# ESD-MATT.net
KiCad netlist of a schematic drawn in Altium Designer
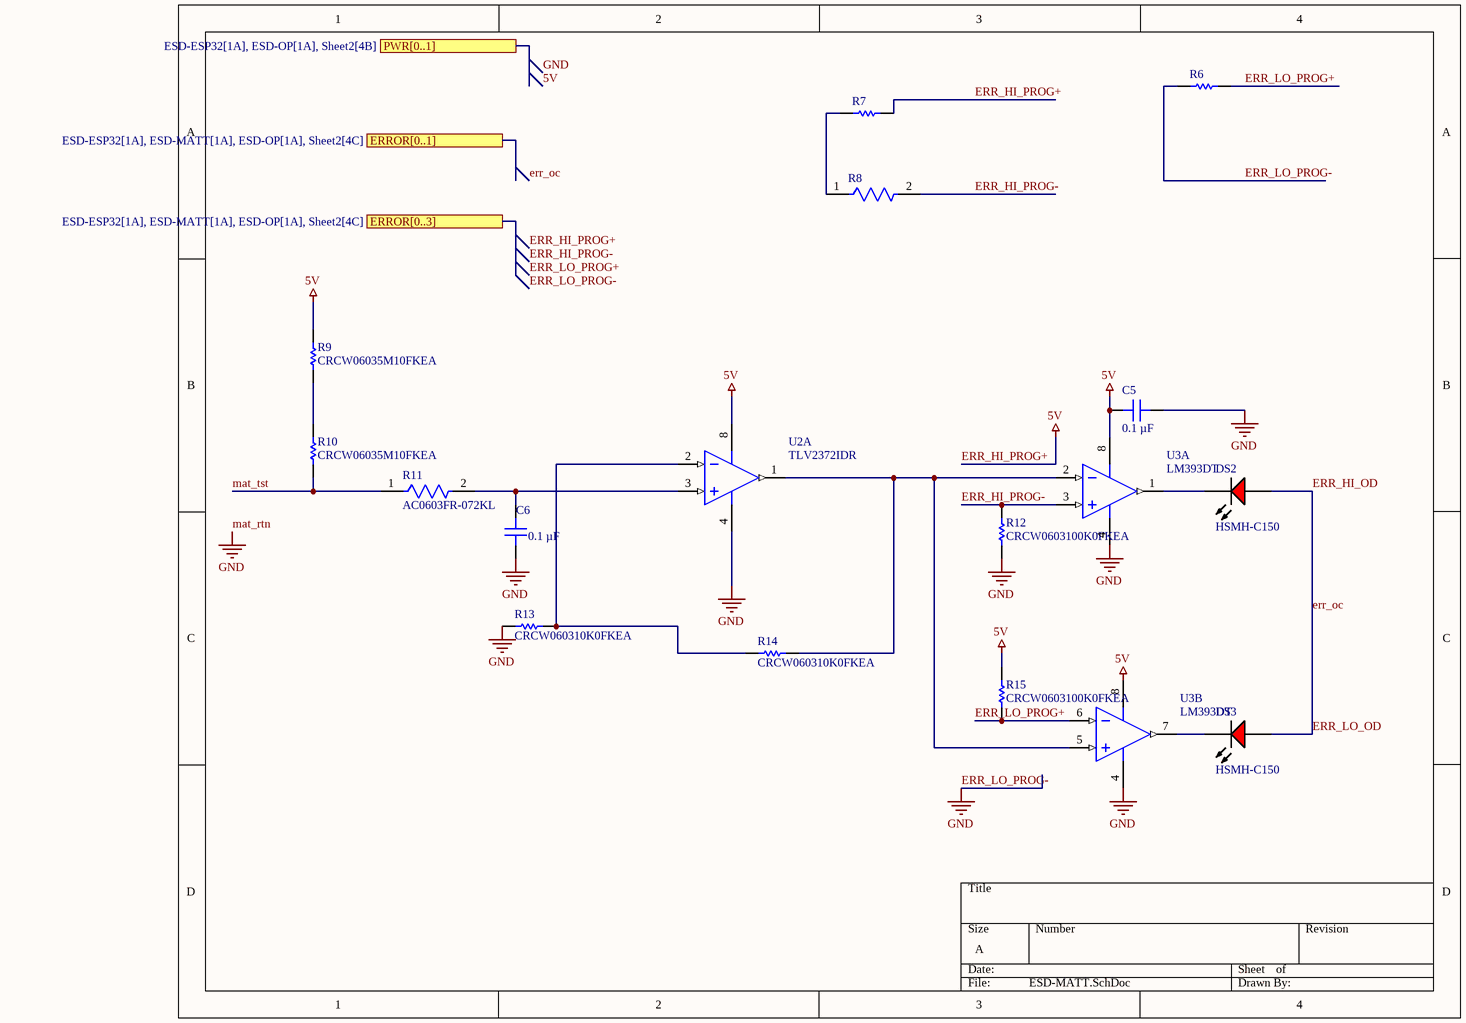
[diagram p0: ESD-MATT.SchDoc]

(export (version "E")
  (design (tool "Eeschema 10.0.6"))
  (components
    (comp (ref "C5")
      (value "0.1 µF")
      (footprint "CAP 0603_1608")
      (description "CAP CER 0.1UF 50V X7R 0603")
      (fields (field (name "PART NUMBER") "C0603X104J5RACAUTO") (field (name "MANUFACTURER") "KEMET"))
      (libsource (lib "Celestial Altium Library - altium_library") (part "Capacitor"))
    )
    (comp (ref "C6")
      (value "0.1 µF")
      (footprint "CAP 0603_1608")
      (description "CAP CER 0.1UF 50V X7R 0603")
      (fields (field (name "PART NUMBER") "C0603X104J5RACAUTO") (field (name "MANUFACTURER") "KEMET"))
      (libsource (lib "Celestial Altium Library - altium_library") (part "Capacitor"))
    )
    (comp (ref "DS2")
      (value "HSMH-C150")
      (footprint "AVAG-HSMX-C150_V")
      (description "LED Uni-Color Red, 65 mW, 25 mA, -40 to 85 degC, 2-Pin SMD, RoHS, Tape and Reel")
      (fields (field (name "MANUFACTURER") "Avago"))
      (libsource (lib "Altium Content Vault") (part "LED-RED-AK-2"))
    )
    (comp (ref "DS3")
      (value "HSMH-C150")
      (footprint "AVAG-HSMX-C150_V")
      (description "LED Uni-Color Red, 65 mW, 25 mA, -40 to 85 degC, 2-Pin SMD, RoHS, Tape and Reel")
      (fields (field (name "MANUFACTURER") "Avago"))
      (libsource (lib "Altium Content Vault") (part "LED-RED-AK-2"))
    )
    (comp (ref "R6")
      (value "CRCW060310K0FKEA")
      (footprint "RESC1609X50X30NL8T20")
      (description "Chip Resistor, 10 KOhm, +/- 1%, 100 mW, -55 to 155 degC, 0603 (1608 Metric), RoHS, Tape and Reel")
      (fields (field (name "MANUFACTURER") "Vishay Semiconductor"))
      (libsource (lib "Altium Content Vault") (part "RES-2"))
    )
    (comp (ref "R7")
      (value "CRCW060310K0FKEA")
      (footprint "RESC1609X50X30NL8T20")
      (description "Chip Resistor, 10 KOhm, +/- 1%, 100 mW, -55 to 155 degC, 0603 (1608 Metric), RoHS, Tape and Reel")
      (fields (field (name "MANUFACTURER") "Vishay Semiconductor"))
      (libsource (lib "Altium Content Vault") (part "RES-2"))
    )
    (comp (ref "R8")
      (value "AC0603FR-072KL")
      (footprint "FP-AC0603-IPC_B")
      (description "RES 2kΩ 1.00% 0.1W 0603")
      (fields (field (name "TOLERANCE") "1%"))
      (libsource (lib "Altium Content Vault") (part "1029c3af85768c4190bb7ad29bc67b5"))
    )
    (comp (ref "R9")
      (value "CRCW06035M10FKEA")
      (footprint "RESC1609X50X30NL10T20")
      (fields (field (name "MANUFACTURER") "Vishay Dale"))
      (libsource (lib "Altium Content Vault") (part "RES"))
    )
    (comp (ref "R10")
      (value "CRCW06035M10FKEA")
      (footprint "RESC1609X50X30NL10T20")
      (fields (field (name "MANUFACTURER") "Vishay Dale"))
      (libsource (lib "Altium Content Vault") (part "RES"))
    )
    (comp (ref "R11")
      (value "AC0603FR-072KL")
      (footprint "FP-AC0603-IPC_B")
      (description "RES 2kΩ 1.00% 0.1W 0603")
      (fields (field (name "TOLERANCE") "1%"))
      (libsource (lib "Altium Content Vault") (part "1029c3af85768c4190bb7ad29bc67b5"))
    )
    (comp (ref "R12")
      (value "CRCW0603100K0FKEA")
      (footprint "RESC1609X50X30NL8T20")
      (description "Chip Resistor, 100 KOhm, +/- 1%, 100 mW, -55 to 155 degC, 0603 (1608 Metric), RoHS, Tape and Reel")
      (fields (field (name "MANUFACTURER") "Vishay Semiconductor"))
      (libsource (lib "Altium Content Vault") (part "RES-2"))
    )
    (comp (ref "R13")
      (value "CRCW060310K0FKEA")
      (footprint "RESC1609X50X30NL8T20")
      (description "Chip Resistor, 10 KOhm, +/- 1%, 100 mW, -55 to 155 degC, 0603 (1608 Metric), RoHS, Tape and Reel")
      (fields (field (name "MANUFACTURER") "Vishay Semiconductor"))
      (libsource (lib "Altium Content Vault") (part "RES-2"))
    )
    (comp (ref "R14")
      (value "CRCW060310K0FKEA")
      (footprint "RESC1609X50X30NL8T20")
      (description "Chip Resistor, 10 KOhm, +/- 1%, 100 mW, -55 to 155 degC, 0603 (1608 Metric), RoHS, Tape and Reel")
      (fields (field (name "MANUFACTURER") "Vishay Semiconductor"))
      (libsource (lib "Altium Content Vault") (part "RES-2"))
    )
    (comp (ref "R15")
      (value "CRCW0603100K0FKEA")
      (footprint "RESC1609X50X30NL8T20")
      (description "Chip Resistor, 100 KOhm, +/- 1%, 100 mW, -55 to 155 degC, 0603 (1608 Metric), RoHS, Tape and Reel")
      (fields (field (name "MANUFACTURER") "Vishay Semiconductor"))
      (libsource (lib "Altium Content Vault") (part "RES-2"))
    )
    (comp (ref "U2")
      (value "TLV2372IDR")
      (footprint "D0008A_M")
      (fields (field (name "MANUFACTURER") "Texas Instruments"))
      (libsource (lib "Altium Content Vault") (part "TI-TLV_TLC-8"))
    )
    (comp (ref "U3")
      (value "LM393DT")
      (footprint "STM-SO-8_D_L")
      (description "Low-Power, Dual-Voltage Comparator, 2 to 36 V, 0 to 70 degC, 8-Pin SOIC (SO), RoHS, Tape and Reel")
      (fields (field (name "MANUFACTURER") "STMicroelectronics"))
      (libsource (lib "Altium Content Vault") (part "STM-LM393-SO8"))
    )
  )
  (nets
    (net (code "9") (name "/ERR_HI_OD") (class "Default")
      (node (ref "DS2") (pin "1") (pinfunction "A_1") (pintype "passive"))
      (node (ref "DS3") (pin "1") (pinfunction "A_1") (pintype "passive"))
    )
    (net (code "10") (name "/ERR_HI_PROG-") (class "Default")
      (node (ref "R12") (pin "1") (pinfunction "1_1") (pintype "passive"))
      (node (ref "R8") (pin "2") (pinfunction "2_2") (pintype "passive"))
      (node (ref "U3") (pin "3") (pinfunction "IN1+_3") (pintype "input"))
    )
    (net (code "11") (name "/ERR_LO_PROG+") (class "Default")
      (node (ref "R15") (pin "2") (pinfunction "2_2") (pintype "passive"))
      (node (ref "R6") (pin "2") (pinfunction "2_2") (pintype "passive"))
      (node (ref "U3") (pin "6") (pinfunction "IN2-_6") (pintype "input"))
    )
    (net (code "13") (name "/mat_tst") (class "Default")
      (node (ref "R10") (pin "1") (pinfunction "1_1") (pintype "passive"))
      (node (ref "R11") (pin "1") (pinfunction "1_1") (pintype "passive"))
    )
    (net (code "14") (name "5V") (class "Default")
      (node (ref "C5") (pin "2") (pinfunction "2_2") (pintype "passive"))
      (node (ref "R15") (pin "1") (pinfunction "1_1") (pintype "passive"))
      (node (ref "R7") (pin "2") (pinfunction "2_2") (pintype "passive"))
      (node (ref "R9") (pin "2") (pinfunction "2_2") (pintype "passive"))
      (node (ref "U2") (pin "8") (pinfunction "VDD_8") (pintype "power_in"))
      (node (ref "U3") (pin "8") (pinfunction "VCC+_8") (pintype "power_in"))
    )
    (net (code "15") (name "GND") (class "Default")
      (node (ref "C5") (pin "1") (pinfunction "1_1") (pintype "passive"))
      (node (ref "C6") (pin "1") (pinfunction "1_1") (pintype "passive"))
      (node (ref "R12") (pin "2") (pinfunction "2_2") (pintype "passive"))
      (node (ref "R13") (pin "1") (pinfunction "1_1") (pintype "passive"))
      (node (ref "R6") (pin "1") (pinfunction "1_1") (pintype "passive"))
      (node (ref "U2") (pin "4") (pinfunction "GND_4") (pintype "power_in"))
      (node (ref "U3") (pin "4") (pinfunction "VCC-_4") (pintype "power_in"))
    )
    (net (code "16") (name "Net-(DS2-K)") (class "Default")
      (node (ref "DS2") (pin "2") (pinfunction "K_2") (pintype "passive"))
      (node (ref "U3") (pin "1") (pinfunction "OUT1_1") (pintype "output"))
    )
    (net (code "17") (name "Net-(DS3-K)") (class "Default")
      (node (ref "DS3") (pin "2") (pinfunction "K_2") (pintype "passive"))
      (node (ref "U3") (pin "7") (pinfunction "OUT2_7") (pintype "output"))
    )
    (net (code "18") (name "Net-(R7-Pad1)") (class "Default")
      (node (ref "R7") (pin "1") (pinfunction "1_1") (pintype "passive"))
      (node (ref "R8") (pin "1") (pinfunction "1_1") (pintype "passive"))
    )
    (net (code "19") (name "Net-(R10-Pad2)") (class "Default")
      (node (ref "R10") (pin "2") (pinfunction "2_2") (pintype "passive"))
      (node (ref "R9") (pin "1") (pinfunction "1_1") (pintype "passive"))
    )
    (net (code "20") (name "Net-(U2A-IN1+)") (class "Default")
      (node (ref "C6") (pin "2") (pinfunction "2_2") (pintype "passive"))
      (node (ref "R11") (pin "2") (pinfunction "2_2") (pintype "passive"))
      (node (ref "U2") (pin "3") (pinfunction "IN1+_3") (pintype "input"))
    )
    (net (code "21") (name "Net-(U2A-IN1-)") (class "Default")
      (node (ref "R13") (pin "2") (pinfunction "2_2") (pintype "passive"))
      (node (ref "R14") (pin "1") (pinfunction "1_1") (pintype "passive"))
      (node (ref "U2") (pin "2") (pinfunction "IN1-_2") (pintype "input"))
    )
    (net (code "22") (name "Net-(U2A-OUT1)") (class "Default")
      (node (ref "R14") (pin "2") (pinfunction "2_2") (pintype "passive"))
      (node (ref "U2") (pin "1") (pinfunction "OUT1_1") (pintype "output"))
      (node (ref "U3") (pin "2") (pinfunction "IN1-_2") (pintype "input"))
      (node (ref "U3") (pin "5") (pinfunction "IN2+_5") (pintype "input"))
    )
  )
)
